# ac-timer-panel.net
KiCad netlist of a schematic drawn in EAGLE
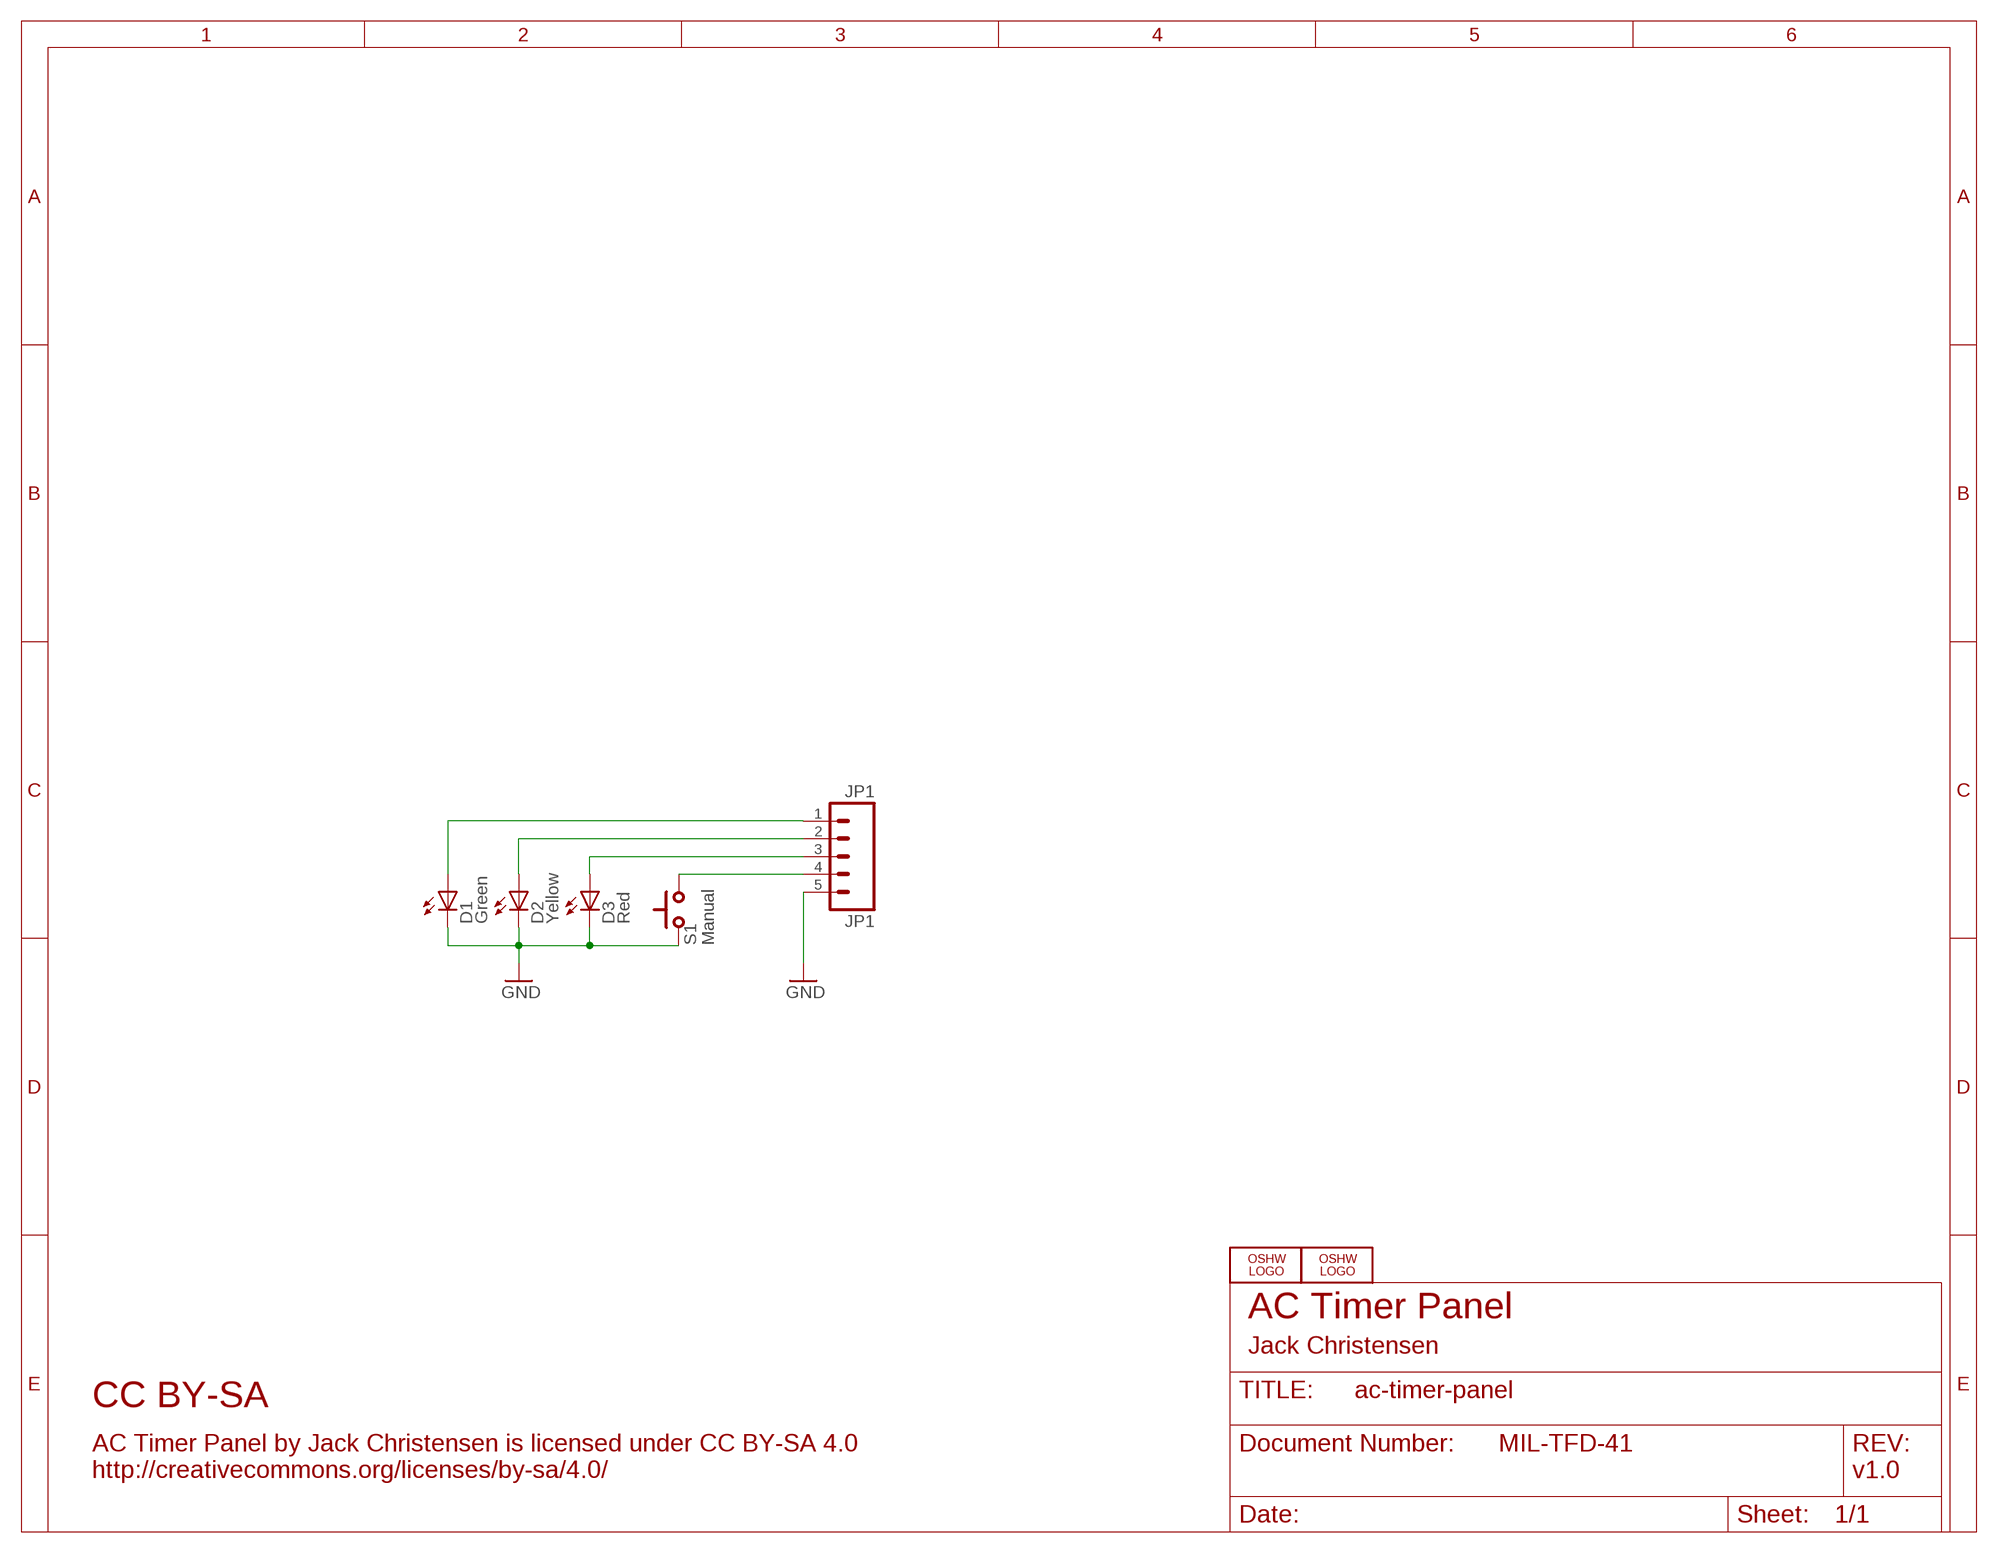
[diagram p0: schematic, sheet 1]

(export (version "E")
  (design (tool "Eeschema 10.0.6"))
  (components
    (comp (ref "D1")
      (value "Green")
      (footprint "eagle-import:LED5MM-OVAL")
      (libsource (lib "eagle-import") (part "LED5MM-LONGPADS"))
    )
    (comp (ref "D2")
      (value "Yellow")
      (footprint "eagle-import:LED5MM-OVAL")
      (libsource (lib "eagle-import") (part "LED5MM-LONGPADS"))
    )
    (comp (ref "D3")
      (value "Red")
      (footprint "eagle-import:LED5MM-OVAL")
      (libsource (lib "eagle-import") (part "LED5MM-LONGPADS"))
    )
    (comp (ref "JP1")
      (value "JP1")
      (footprint "eagle-import:1X05_LOCK")
      (libsource (lib "eagle-import") (part "M05LOCK"))
    )
    (comp (ref "LOGO1")
      (value "OSHW_LOGO_8MILX0100-NT")
      (footprint "eagle-import:OSHW_8X100_NOTEXT")
      (libsource (lib "eagle-import") (part "OSHW_LOGO_8MILX0100-NT"))
    )
    (comp (ref "LOGO2")
      (value "OSHW_LOGO_8MILX0100-NT")
      (footprint "eagle-import:OSHW_8X100_NOTEXT")
      (libsource (lib "eagle-import") (part "OSHW_LOGO_8MILX0100-NT"))
    )
    (comp (ref "S1")
      (value "Manual")
      (footprint "eagle-import:SPST-NO-MC")
      (libsource (lib "eagle-import") (part "SPST-NO-MCPUSHBUTTON"))
    )
  )
  (nets
    (net (code "1") (name "GND") (class "Default")
      (node (ref "D1") (pin "K") (pinfunction "C_K") (pintype "passive"))
      (node (ref "D2") (pin "K") (pinfunction "C_K") (pintype "passive"))
      (node (ref "D3") (pin "K") (pinfunction "C_K") (pintype "passive"))
      (node (ref "JP1") (pin "5") (pinfunction "5_5") (pintype "passive"))
      (node (ref "S1") (pin "P$2") (pinfunction "P$2_P$2") (pintype "bidirectional"))
    )
    (net (code "2") (name "Net-(D1-PadA)") (class "Default")
      (node (ref "D1") (pin "A") (pinfunction "A_A") (pintype "passive"))
      (node (ref "JP1") (pin "1") (pinfunction "1_1") (pintype "passive"))
    )
    (net (code "3") (name "Net-(D2-PadA)") (class "Default")
      (node (ref "D2") (pin "A") (pinfunction "A_A") (pintype "passive"))
      (node (ref "JP1") (pin "2") (pinfunction "2_2") (pintype "passive"))
    )
    (net (code "4") (name "Net-(D3-PadA)") (class "Default")
      (node (ref "D3") (pin "A") (pinfunction "A_A") (pintype "passive"))
      (node (ref "JP1") (pin "3") (pinfunction "3_3") (pintype "passive"))
    )
    (net (code "5") (name "Net-(JP1-Pad4)") (class "Default")
      (node (ref "JP1") (pin "4") (pinfunction "4_4") (pintype "passive"))
      (node (ref "S1") (pin "P$1") (pinfunction "P$1_P$1") (pintype "bidirectional"))
    )
  )
)
